# Micro.net
KiCad netlist of a schematic drawn in Altium Designer
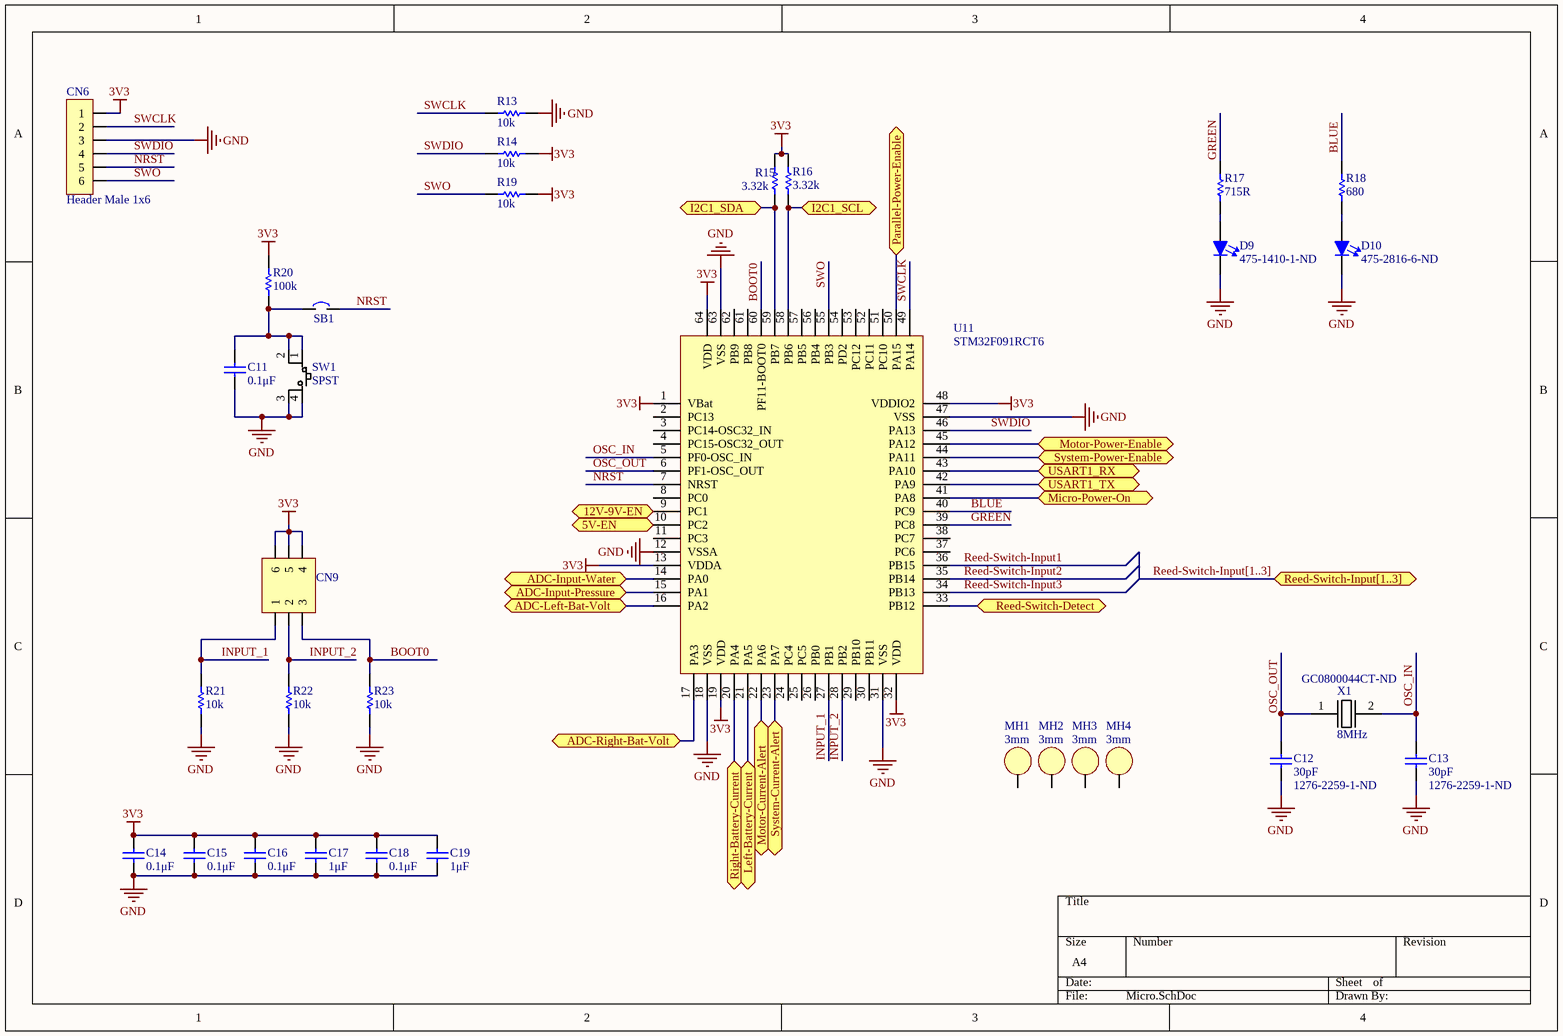
[diagram p0: Micro.SchDoc]

(export (version "E")
  (design (tool "Eeschema 10.0.6"))
  (components
    (comp (ref "C11")
      (value "0.1μF")
      (footprint "CAPC1608N(0603\")")
      (description "Capacitor, Ceramic, 100V, +/- 10%, 0603 SMD, X7R")
      (fields
        (field (name "MFG") "TDK")
        (field (name "PUBLISHER") "AUVic")
        (field (name "CREATED BY") "Ashwin Sira")
      )
      (libsource (lib "AUVic_Integrated_Library_Capacitors") (part "0.1uF 100V 0603 SMD, Ceramic"))
    )
    (comp (ref "C12")
      (value "30pF")
      (footprint "CAPC1608N(0603\")")
      (description "Capacitor, Ceramic, 50V, +/-1%, 0603 SMD, C0G")
      (fields
        (field (name "SUPPLIER PART NUMBER 1") "1276-2259-1-ND")
        (field (name "PUBLISHER") "AUVic")
        (field (name "MADE BY") "Andy Bates")
      )
      (libsource (lib "AUVic_Integrated_Library_Capacitors") (part "30pF 50V 0603 SMD, Ceramic"))
    )
    (comp (ref "C13")
      (value "30pF")
      (footprint "CAPC1608N(0603\")")
      (description "Capacitor, Ceramic, 50V, +/-1%, 0603 SMD, C0G")
      (fields
        (field (name "SUPPLIER PART NUMBER 1") "1276-2259-1-ND")
        (field (name "PUBLISHER") "AUVic")
        (field (name "MADE BY") "Andy Bates")
      )
      (libsource (lib "AUVic_Integrated_Library_Capacitors") (part "30pF 50V 0603 SMD, Ceramic"))
    )
    (comp (ref "C14")
      (value "0.1μF")
      (footprint "CAPC1608N(0603\")")
      (description "Capacitor, Ceramic, 100V, +/- 10%, 0603 SMD, X7R")
      (fields
        (field (name "MFG") "TDK")
        (field (name "PUBLISHER") "AUVic")
        (field (name "CREATED BY") "Ashwin Sira")
      )
      (libsource (lib "AUVic_Integrated_Library_Capacitors") (part "0.1uF 100V 0603 SMD, Ceramic"))
    )
    (comp (ref "C15")
      (value "0.1μF")
      (footprint "CAPC1608N(0603\")")
      (description "Capacitor, Ceramic, 100V, +/- 10%, 0603 SMD, X7R")
      (fields
        (field (name "MFG") "TDK")
        (field (name "PUBLISHER") "AUVic")
        (field (name "CREATED BY") "Ashwin Sira")
      )
      (libsource (lib "AUVic_Integrated_Library_Capacitors") (part "0.1uF 100V 0603 SMD, Ceramic"))
    )
    (comp (ref "C16")
      (value "0.1μF")
      (footprint "CAPC1608N(0603\")")
      (description "Capacitor, Ceramic, 100V, +/- 10%, 0603 SMD, X7R")
      (fields
        (field (name "MFG") "TDK")
        (field (name "PUBLISHER") "AUVic")
        (field (name "CREATED BY") "Ashwin Sira")
      )
      (libsource (lib "AUVic_Integrated_Library_Capacitors") (part "0.1uF 100V 0603 SMD, Ceramic"))
    )
    (comp (ref "C17")
      (value "1μF")
      (footprint "CAPC1608N(0603\")")
      (description "Capacitor, Ceramic, 25V, +/- 10%, 0603 SMD, X5R")
      (fields
        (field (name "MFG") "Murata-Electronics-North-America")
        (field (name "PUBLISHER") "AUVic")
        (field (name "CREATED BY") "Andy Bates")
      )
      (libsource (lib "AUVic_Integrated_Library_Capacitors") (part "1uF 25V 0603 SMD, Ceramic"))
    )
    (comp (ref "C18")
      (value "0.1μF")
      (footprint "CAPC1608N(0603\")")
      (description "Capacitor, Ceramic, 100V, +/- 10%, 0603 SMD, X7R")
      (fields
        (field (name "MFG") "TDK")
        (field (name "PUBLISHER") "AUVic")
        (field (name "CREATED BY") "Ashwin Sira")
      )
      (libsource (lib "AUVic_Integrated_Library_Capacitors") (part "0.1uF 100V 0603 SMD, Ceramic"))
    )
    (comp (ref "C19")
      (value "1μF")
      (footprint "CAPC1608N(0603\")")
      (description "Capacitor, Ceramic, 25V, +/- 10%, 0603 SMD, X5R")
      (fields
        (field (name "MFG") "Murata-Electronics-North-America")
        (field (name "PUBLISHER") "AUVic")
        (field (name "CREATED BY") "Andy Bates")
      )
      (libsource (lib "AUVic_Integrated_Library_Capacitors") (part "1uF 25V 0603 SMD, Ceramic"))
    )
    (comp (ref "CN6")
      (value "Header Male 1x6")
      (footprint "Header, Male, 1X6")
      (description "1x6, Pads Pitch: 0.1\" (2.54mm), Through hole")
      (libsource (lib "AUVic_Integrated_Library_Connectors") (part "Header, Male, 1x6"))
    )
    (comp (ref "CN9")
      (value "Header, Male, 2x3, Pitch: 0.1\" (2.54mm), THT")
      (footprint "Header, Male, 2x3, Pitch: 0.1\" (2.54mm),THT")
      (fields
        (field (name "PUBLISHER") "AUVic")
        (field (name "REVIEWED BY") "*")
        (field (name "CREATED BY") "Andy Bates")
      )
      (libsource (lib "AUVic_Integrated_Library_Connectors") (part "Header, Male, 2x3, Pitch{colon} 0.1{dblquote} (2.54mm), THT"))
    )
    (comp (ref "D9")
      (value "Red")
      (footprint "LED0805")
      (description "LED, 0805 (2012), Green, Clear")
      (fields
        (field (name "SUPPLIER PART NUMBER 1") "475-1410-1-ND")
        (field (name "CREATED BY") "Andy Bates")
      )
      (libsource (lib "AUVic_Integrated_Library_Diodes") (part "LED, 0805 (2012), Green, Clear"))
    )
    (comp (ref "D10")
      (value "Blue")
      (footprint "LED0603")
      (description "LED, 0603 (1608), Blue, Clear")
      (fields
        (field (name "SUPPLIER PART NUMBER 1") "475-2816-6-ND")
        (field (name "CREATED BY") "Lyden Smith")
      )
      (libsource (lib "AUVic_Integrated_Library_Diodes") (part "LED, 0603 (1608), Blue, Clear"))
    )
    (comp (ref "MH1")
      (value "3mm")
      (footprint "Mount-Hole_3mm")
      (libsource (lib "AUVic_Integrated_Library_Connectors") (part "Mount_Hole_3mm"))
    )
    (comp (ref "MH2")
      (value "3mm")
      (footprint "Mount-Hole_3mm")
      (libsource (lib "AUVic_Integrated_Library_Connectors") (part "Mount_Hole_3mm"))
    )
    (comp (ref "MH3")
      (value "3mm")
      (footprint "Mount-Hole_3mm")
      (libsource (lib "AUVic_Integrated_Library_Connectors") (part "Mount_Hole_3mm"))
    )
    (comp (ref "MH4")
      (value "3mm")
      (footprint "Mount-Hole_3mm")
      (libsource (lib "AUVic_Integrated_Library_Connectors") (part "Mount_Hole_3mm"))
    )
    (comp (ref "R13")
      (value "10k")
      (footprint "RESC1608N(0603\")")
      (description "10kR, 1%, 1/10W, 0603 SMD")
      (fields (field (name "MADE BY") "Ashwin Sira"))
      (libsource (lib "AUVic_Integrated_Library_Resistors") (part "10kR, 1%, 1/10W, 0603 SMD"))
    )
    (comp (ref "R14")
      (value "10k")
      (footprint "RESC1608N(0603\")")
      (description "10kR, 1%, 1/10W, 0603 SMD")
      (fields (field (name "MADE BY") "Ashwin Sira"))
      (libsource (lib "AUVic_Integrated_Library_Resistors") (part "10kR, 1%, 1/10W, 0603 SMD"))
    )
    (comp (ref "R15")
      (value "3.32k")
      (footprint "RESC1608N(0603\")")
      (description "3.32k, 1%, 1/10W, 0603, SMD")
      (fields (field (name "CREATED BY") "Ashwin Sira") (field (name "PUBLISHER") "AUVic"))
      (libsource (lib "AUVic_Integrated_Library_Resistors") (part "3.32k, 1%, 1/10W, 0603, SMD"))
    )
    (comp (ref "R16")
      (value "3.32k")
      (footprint "RESC1608N(0603\")")
      (description "3.32k, 1%, 1/10W, 0603, SMD")
      (fields (field (name "CREATED BY") "Ashwin Sira") (field (name "PUBLISHER") "AUVic"))
      (libsource (lib "AUVic_Integrated_Library_Resistors") (part "3.32k, 1%, 1/10W, 0603, SMD"))
    )
    (comp (ref "R17")
      (value "715R")
      (footprint "RESC1608N(0603\")")
      (description "715R, 1%, 1/10W, 0603, SMD")
      (fields (field (name "CREATED BY") "Ashwin Sira") (field (name "PUBLISHER") "AUVic"))
      (libsource (lib "AUVic_Integrated_Library_Resistors") (part "715R, 1%, 1/10W, 0603, SMD"))
    )
    (comp (ref "R18")
      (value "680")
      (footprint "RESC2012N(0805\")")
      (description "680, 5%, 1/8W, 0805 SMD")
      (fields (field (name "CREATED BY") "Lyden Smith"))
      (libsource (lib "AUVic_Integrated_Library_Resistors") (part "680, 5%, 1/8W, 0805 SMD"))
    )
    (comp (ref "R19")
      (value "10k")
      (footprint "RESC1608N(0603\")")
      (description "10kR, 1%, 1/10W, 0603 SMD")
      (fields (field (name "MADE BY") "Ashwin Sira"))
      (libsource (lib "AUVic_Integrated_Library_Resistors") (part "10kR, 1%, 1/10W, 0603 SMD"))
    )
    (comp (ref "R20")
      (value "100k")
      (footprint "RESC1608N(0603\")")
      (description "100kR, 1%, 1/10W, 0603 SMD")
      (fields (field (name "MADE BY") "Andy Bates"))
      (libsource (lib "AUVic_Integrated_Library_Resistors") (part "100kR, 1%, 1/10W, 0603 SMD"))
    )
    (comp (ref "R21")
      (value "10k")
      (footprint "RESC1608N(0603\")")
      (description "10kR, 1%, 1/10W, 0603 SMD")
      (fields (field (name "MADE BY") "Ashwin Sira"))
      (libsource (lib "AUVic_Integrated_Library_Resistors") (part "10kR, 1%, 1/10W, 0603 SMD"))
    )
    (comp (ref "R22")
      (value "10k")
      (footprint "RESC1608N(0603\")")
      (description "10kR, 1%, 1/10W, 0603 SMD")
      (fields (field (name "MADE BY") "Ashwin Sira"))
      (libsource (lib "AUVic_Integrated_Library_Resistors") (part "10kR, 1%, 1/10W, 0603 SMD"))
    )
    (comp (ref "R23")
      (value "10k")
      (footprint "RESC1608N(0603\")")
      (description "10kR, 1%, 1/10W, 0603 SMD")
      (fields (field (name "MADE BY") "Ashwin Sira"))
      (libsource (lib "AUVic_Integrated_Library_Resistors") (part "10kR, 1%, 1/10W, 0603 SMD"))
    )
    (comp (ref "SB1")
      (value "Solder Bridge")
      (footprint "Solder Bridge")
      (fields (field (name "MADE BY") "Andy Bates"))
      (libsource (lib "AUVic_Integrated_Library_Connectors") (part "Solder Bridge"))
    )
    (comp (ref "SW1")
      (value "SPST")
      (footprint "4-SPST-NO")
      (fields (field (name "MADE BY") "Andy Bates"))
      (libsource (lib "AUVic_Integrated_Library_Switches") (part "4 pin Tacitle Switch"))
    )
    (comp (ref "U11")
      (value "STM32F091RCT6")
      (footprint "STM-LQFP64_N")
      (fields (field (name "MADE BY") "Andy Bates"))
      (libsource (lib "AUVic_Integrated_Library_Microprocessors") (part "STM32F091RCT6"))
    )
    (comp (ref "X1")
      (value "8MHz")
      (footprint "HC49/US")
      (description "8Mhz 40ESR  16pF -20°C ~ 70°C")
      (fields (field (name "SUPPLIER PART NUMBER 1") "GC0800044CT-ND") (field (name "MADE BY") "Lyden Smith"))
      (libsource (lib "AUVic_Integrated_Library_Oscillators") (part "Oscillator 8MHz 40ESR"))
    )
  )
  (nets
    (net (code "1") (name "/5V-EN") (class "Default")
      (node (ref "U11") (pin "10") (pinfunction "PC2_10") (pintype "passive"))
    )
    (net (code "2") (name "/12V-9V-EN") (class "Default")
      (node (ref "U11") (pin "9") (pinfunction "PC1_9") (pintype "passive"))
    )
    (net (code "3") (name "/ADC-Input-Pressure") (class "Default")
      (node (ref "U11") (pin "15") (pinfunction "PA1_15") (pintype "passive"))
    )
    (net (code "4") (name "/ADC-Input-Water") (class "Default")
      (node (ref "U11") (pin "14") (pinfunction "PA0_14") (pintype "passive"))
    )
    (net (code "5") (name "/ADC-Left-Bat-Volt") (class "Default")
      (node (ref "U11") (pin "16") (pinfunction "PA2_16") (pintype "passive"))
    )
    (net (code "6") (name "/ADC-Right-Bat-Volt") (class "Default")
      (node (ref "U11") (pin "17") (pinfunction "PA3_17") (pintype "passive"))
    )
    (net (code "7") (name "/BLUE") (class "Default")
      (node (ref "R18") (pin "2") (pinfunction "2_2") (pintype "passive"))
      (node (ref "U11") (pin "40") (pinfunction "PC9_40") (pintype "passive"))
    )
    (net (code "8") (name "/BOOT0") (class "Default")
      (node (ref "CN9") (pin "3") (pinfunction "3_3") (pintype "passive"))
      (node (ref "R23") (pin "2") (pinfunction "2_2") (pintype "passive"))
      (node (ref "U11") (pin "60") (pinfunction "PF11-BOOT0_60") (pintype "passive"))
    )
    (net (code "9") (name "/GREEN") (class "Default")
      (node (ref "R17") (pin "2") (pinfunction "2_2") (pintype "passive"))
      (node (ref "U11") (pin "39") (pinfunction "PC8_39") (pintype "passive"))
    )
    (net (code "10") (name "/I2C1_SCL") (class "Default")
      (node (ref "R16") (pin "2") (pinfunction "2_2") (pintype "passive"))
      (node (ref "U11") (pin "58") (pinfunction "PB6_58") (pintype "passive"))
    )
    (net (code "11") (name "/I2C1_SDA") (class "Default")
      (node (ref "R15") (pin "2") (pinfunction "2_2") (pintype "passive"))
      (node (ref "U11") (pin "59") (pinfunction "PB7_59") (pintype "passive"))
    )
    (net (code "12") (name "/INPUT_1") (class "Default")
      (node (ref "CN9") (pin "1") (pinfunction "1_1") (pintype "passive"))
      (node (ref "R21") (pin "2") (pinfunction "2_2") (pintype "passive"))
      (node (ref "U11") (pin "27") (pinfunction "PB1_27") (pintype "passive"))
    )
    (net (code "13") (name "/INPUT_2") (class "Default")
      (node (ref "CN9") (pin "2") (pinfunction "2_2") (pintype "passive"))
      (node (ref "R22") (pin "2") (pinfunction "2_2") (pintype "passive"))
      (node (ref "U11") (pin "28") (pinfunction "PB2_28") (pintype "passive"))
    )
    (net (code "14") (name "/Left-Battery-Current") (class "Default")
      (node (ref "U11") (pin "21") (pinfunction "PA5_21") (pintype "passive"))
    )
    (net (code "15") (name "/Micro-Power-On") (class "Default")
      (node (ref "U11") (pin "41") (pinfunction "PA8_41") (pintype "passive"))
    )
    (net (code "16") (name "/Motor-Current-Alert") (class "Default")
      (node (ref "U11") (pin "22") (pinfunction "PA6_22") (pintype "passive"))
    )
    (net (code "17") (name "/Motor-Power-Enable") (class "Default")
      (node (ref "U11") (pin "45") (pinfunction "PA12_45") (pintype "passive"))
    )
    (net (code "18") (name "/NRST") (class "Default")
      (node (ref "CN6") (pin "5") (pinfunction "5_5") (pintype "passive"))
      (node (ref "SB1") (pin "2") (pinfunction "2_2") (pintype "passive"))
      (node (ref "U11") (pin "7") (pinfunction "NRST_7") (pintype "passive"))
    )
    (net (code "19") (name "/OSC_IN") (class "Default")
      (node (ref "C13") (pin "2") (pinfunction "2_2") (pintype "passive"))
      (node (ref "U11") (pin "5") (pinfunction "PF0-OSC_IN_5") (pintype "passive"))
      (node (ref "X1") (pin "2") (pinfunction "2_2") (pintype "passive"))
    )
    (net (code "20") (name "/OSC_OUT") (class "Default")
      (node (ref "C12") (pin "2") (pinfunction "2_2") (pintype "passive"))
      (node (ref "U11") (pin "6") (pinfunction "PF1-OSC_OUT_6") (pintype "passive"))
      (node (ref "X1") (pin "1") (pinfunction "1_1") (pintype "passive"))
    )
    (net (code "21") (name "/Parallel-Power-Enable") (class "Default")
      (node (ref "U11") (pin "50") (pinfunction "PA15_50") (pintype "passive"))
    )
    (net (code "22") (name "/Reed-Switch-Detect") (class "Default")
      (node (ref "U11") (pin "33") (pinfunction "PB12_33") (pintype "passive"))
    )
    (net (code "23") (name "/Reed-Switch-Input1") (class "Default")
      (node (ref "U11") (pin "36") (pinfunction "PB15_36") (pintype "passive"))
    )
    (net (code "24") (name "/Reed-Switch-Input2") (class "Default")
      (node (ref "U11") (pin "35") (pinfunction "PB14_35") (pintype "passive"))
    )
    (net (code "25") (name "/Reed-Switch-Input3") (class "Default")
      (node (ref "U11") (pin "34") (pinfunction "PB13_34") (pintype "passive"))
    )
    (net (code "27") (name "/Right-Battery-Current") (class "Default")
      (node (ref "U11") (pin "20") (pinfunction "PA4_20") (pintype "passive"))
    )
    (net (code "28") (name "/SWCLK") (class "Default")
      (node (ref "CN6") (pin "2") (pinfunction "2_2") (pintype "passive"))
      (node (ref "R13") (pin "2") (pinfunction "2_2") (pintype "passive"))
      (node (ref "U11") (pin "49") (pinfunction "PA14_49") (pintype "passive"))
    )
    (net (code "29") (name "/SWDIO") (class "Default")
      (node (ref "CN6") (pin "4") (pinfunction "4_4") (pintype "passive"))
      (node (ref "R14") (pin "1") (pinfunction "1_1") (pintype "passive"))
      (node (ref "U11") (pin "46") (pinfunction "PA13_46") (pintype "passive"))
    )
    (net (code "30") (name "/SWO") (class "Default")
      (node (ref "CN6") (pin "6") (pinfunction "6_6") (pintype "passive"))
      (node (ref "R19") (pin "1") (pinfunction "1_1") (pintype "passive"))
      (node (ref "U11") (pin "55") (pinfunction "PB3_55") (pintype "passive"))
    )
    (net (code "31") (name "/System-Current-Alert") (class "Default")
      (node (ref "U11") (pin "23") (pinfunction "PA7_23") (pintype "passive"))
    )
    (net (code "32") (name "/System-Power-Enable") (class "Default")
      (node (ref "U11") (pin "44") (pinfunction "PA11_44") (pintype "passive"))
    )
    (net (code "33") (name "/USART1_RX") (class "Default")
      (node (ref "U11") (pin "43") (pinfunction "PA10_43") (pintype "passive"))
    )
    (net (code "34") (name "/USART1_TX") (class "Default")
      (node (ref "U11") (pin "42") (pinfunction "PA9_42") (pintype "passive"))
    )
    (net (code "35") (name "3V3") (class "Default")
      (node (ref "C14") (pin "2") (pinfunction "Cathode_2") (pintype "passive"))
      (node (ref "C15") (pin "2") (pinfunction "Cathode_2") (pintype "passive"))
      (node (ref "C16") (pin "2") (pinfunction "Cathode_2") (pintype "passive"))
      (node (ref "C17") (pin "2") (pinfunction "Cathode_2") (pintype "passive"))
      (node (ref "C18") (pin "2") (pinfunction "Cathode_2") (pintype "passive"))
      (node (ref "C19") (pin "2") (pinfunction "Cathode_2") (pintype "passive"))
      (node (ref "CN6") (pin "1") (pinfunction "1_1") (pintype "passive"))
      (node (ref "CN9") (pin "4") (pinfunction "4_4") (pintype "passive"))
      (node (ref "CN9") (pin "5") (pinfunction "5_5") (pintype "passive"))
      (node (ref "CN9") (pin "6") (pinfunction "6_6") (pintype "passive"))
      (node (ref "R14") (pin "2") (pinfunction "2_2") (pintype "passive"))
      (node (ref "R15") (pin "1") (pinfunction "1_1") (pintype "passive"))
      (node (ref "R16") (pin "1") (pinfunction "1_1") (pintype "passive"))
      (node (ref "R19") (pin "2") (pinfunction "2_2") (pintype "passive"))
      (node (ref "R20") (pin "2") (pinfunction "2_2") (pintype "passive"))
      (node (ref "U11") (pin "1") (pinfunction "VBat_1") (pintype "passive"))
      (node (ref "U11") (pin "13") (pinfunction "VDDA_13") (pintype "passive"))
      (node (ref "U11") (pin "19") (pinfunction "VDD_19") (pintype "passive"))
      (node (ref "U11") (pin "32") (pinfunction "VDD_32") (pintype "passive"))
      (node (ref "U11") (pin "48") (pinfunction "VDDIO2_48") (pintype "passive"))
      (node (ref "U11") (pin "64") (pinfunction "VDD_64") (pintype "passive"))
    )
    (net (code "36") (name "GND") (class "Default")
      (node (ref "C11") (pin "1") (pinfunction "Anode_1") (pintype "passive"))
      (node (ref "C12") (pin "1") (pinfunction "1_1") (pintype "passive"))
      (node (ref "C13") (pin "1") (pinfunction "1_1") (pintype "passive"))
      (node (ref "C14") (pin "1") (pinfunction "Anode_1") (pintype "passive"))
      (node (ref "C15") (pin "1") (pinfunction "Anode_1") (pintype "passive"))
      (node (ref "C16") (pin "1") (pinfunction "Anode_1") (pintype "passive"))
      (node (ref "C17") (pin "1") (pinfunction "Anode_1") (pintype "passive"))
      (node (ref "C18") (pin "1") (pinfunction "Anode_1") (pintype "passive"))
      (node (ref "C19") (pin "1") (pinfunction "Anode_1") (pintype "passive"))
      (node (ref "CN6") (pin "3") (pinfunction "3_3") (pintype "passive"))
      (node (ref "D10") (pin "1") (pinfunction "Cathode_1") (pintype "passive"))
      (node (ref "D9") (pin "1") (pinfunction "Cathode_1") (pintype "passive"))
      (node (ref "R13") (pin "1") (pinfunction "1_1") (pintype "passive"))
      (node (ref "R21") (pin "1") (pinfunction "1_1") (pintype "passive"))
      (node (ref "R22") (pin "1") (pinfunction "1_1") (pintype "passive"))
      (node (ref "R23") (pin "1") (pinfunction "1_1") (pintype "passive"))
      (node (ref "SW1") (pin "3") (pinfunction "3_3") (pintype "passive"))
      (node (ref "SW1") (pin "4") (pinfunction "4_4") (pintype "passive"))
      (node (ref "U11") (pin "12") (pinfunction "VSSA_12") (pintype "passive"))
      (node (ref "U11") (pin "18") (pinfunction "VSS_18") (pintype "passive"))
      (node (ref "U11") (pin "31") (pinfunction "VSS_31") (pintype "passive"))
      (node (ref "U11") (pin "47") (pinfunction "VSS_47") (pintype "passive"))
      (node (ref "U11") (pin "63") (pinfunction "VSS_63") (pintype "passive"))
    )
    (net (code "37") (name "Net-(C11-Cathode)") (class "Default")
      (node (ref "C11") (pin "2") (pinfunction "Cathode_2") (pintype "passive"))
      (node (ref "R20") (pin "1") (pinfunction "1_1") (pintype "passive"))
      (node (ref "SB1") (pin "1") (pinfunction "1_1") (pintype "passive"))
      (node (ref "SW1") (pin "1") (pinfunction "1_1") (pintype "passive"))
      (node (ref "SW1") (pin "2") (pinfunction "2_2") (pintype "passive"))
    )
    (net (code "38") (name "Net-(D9-Anode)") (class "Default")
      (node (ref "D9") (pin "2") (pinfunction "Anode_2") (pintype "passive"))
      (node (ref "R17") (pin "1") (pinfunction "1_1") (pintype "passive"))
    )
    (net (code "39") (name "Net-(D10-Anode)") (class "Default")
      (node (ref "D10") (pin "2") (pinfunction "Anode_2") (pintype "passive"))
      (node (ref "R18") (pin "1") (pinfunction "1_1") (pintype "passive"))
    )
    (net (code "40") (name "unconnected-(MH1-Pad1)") (class "Default")
      (node (ref "MH1") (pin "1") (pinfunction "1_1") (pintype "passive"))
    )
    (net (code "41") (name "unconnected-(MH2-Pad1)") (class "Default")
      (node (ref "MH2") (pin "1") (pinfunction "1_1") (pintype "passive"))
    )
    (net (code "42") (name "unconnected-(MH3-Pad1)") (class "Default")
      (node (ref "MH3") (pin "1") (pinfunction "1_1") (pintype "passive"))
    )
    (net (code "43") (name "unconnected-(MH4-Pad1)") (class "Default")
      (node (ref "MH4") (pin "1") (pinfunction "1_1") (pintype "passive"))
    )
    (net (code "44") (name "unconnected-(U11-PB0-Pad26)") (class "Default")
      (node (ref "U11") (pin "26") (pinfunction "PB0_26") (pintype "passive"))
    )
    (net (code "45") (name "unconnected-(U11-PB4-Pad56)") (class "Default")
      (node (ref "U11") (pin "56") (pinfunction "PB4_56") (pintype "passive"))
    )
    (net (code "46") (name "unconnected-(U11-PB5-Pad57)") (class "Default")
      (node (ref "U11") (pin "57") (pinfunction "PB5_57") (pintype "passive"))
    )
    (net (code "47") (name "unconnected-(U11-PB8-Pad61)") (class "Default")
      (node (ref "U11") (pin "61") (pinfunction "PB8_61") (pintype "passive"))
    )
    (net (code "48") (name "unconnected-(U11-PB9-Pad62)") (class "Default")
      (node (ref "U11") (pin "62") (pinfunction "PB9_62") (pintype "passive"))
    )
    (net (code "49") (name "unconnected-(U11-PB10-Pad29)") (class "Default")
      (node (ref "U11") (pin "29") (pinfunction "PB10_29") (pintype "passive"))
    )
    (net (code "50") (name "unconnected-(U11-PB11-Pad30)") (class "Default")
      (node (ref "U11") (pin "30") (pinfunction "PB11_30") (pintype "passive"))
    )
    (net (code "51") (name "unconnected-(U11-PC0-Pad8)") (class "Default")
      (node (ref "U11") (pin "8") (pinfunction "PC0_8") (pintype "passive"))
    )
    (net (code "52") (name "unconnected-(U11-PC3-Pad11)") (class "Default")
      (node (ref "U11") (pin "11") (pinfunction "PC3_11") (pintype "passive"))
    )
    (net (code "53") (name "unconnected-(U11-PC4-Pad24)") (class "Default")
      (node (ref "U11") (pin "24") (pinfunction "PC4_24") (pintype "passive"))
    )
    (net (code "54") (name "unconnected-(U11-PC5-Pad25)") (class "Default")
      (node (ref "U11") (pin "25") (pinfunction "PC5_25") (pintype "passive"))
    )
    (net (code "55") (name "unconnected-(U11-PC6-Pad37)") (class "Default")
      (node (ref "U11") (pin "37") (pinfunction "PC6_37") (pintype "passive"))
    )
    (net (code "56") (name "unconnected-(U11-PC7-Pad38)") (class "Default")
      (node (ref "U11") (pin "38") (pinfunction "PC7_38") (pintype "passive"))
    )
    (net (code "57") (name "unconnected-(U11-PC10-Pad51)") (class "Default")
      (node (ref "U11") (pin "51") (pinfunction "PC10_51") (pintype "passive"))
    )
    (net (code "58") (name "unconnected-(U11-PC11-Pad52)") (class "Default")
      (node (ref "U11") (pin "52") (pinfunction "PC11_52") (pintype "passive"))
    )
    (net (code "59") (name "unconnected-(U11-PC12-Pad53)") (class "Default")
      (node (ref "U11") (pin "53") (pinfunction "PC12_53") (pintype "passive"))
    )
    (net (code "60") (name "unconnected-(U11-PC13-Pad2)") (class "Default")
      (node (ref "U11") (pin "2") (pinfunction "PC13_2") (pintype "passive"))
    )
    (net (code "61") (name "unconnected-(U11-PC14-OSC32_IN-Pad3)") (class "Default")
      (node (ref "U11") (pin "3") (pinfunction "PC14-OSC32_IN_3") (pintype "passive"))
    )
    (net (code "62") (name "unconnected-(U11-PC15-OSC32_OUT-Pad4)") (class "Default")
      (node (ref "U11") (pin "4") (pinfunction "PC15-OSC32_OUT_4") (pintype "passive"))
    )
    (net (code "63") (name "unconnected-(U11-PD2-Pad54)") (class "Default")
      (node (ref "U11") (pin "54") (pinfunction "PD2_54") (pintype "passive"))
    )
  )
)
